# TSAL.net
KiCad netlist of a schematic drawn in Altium Designer
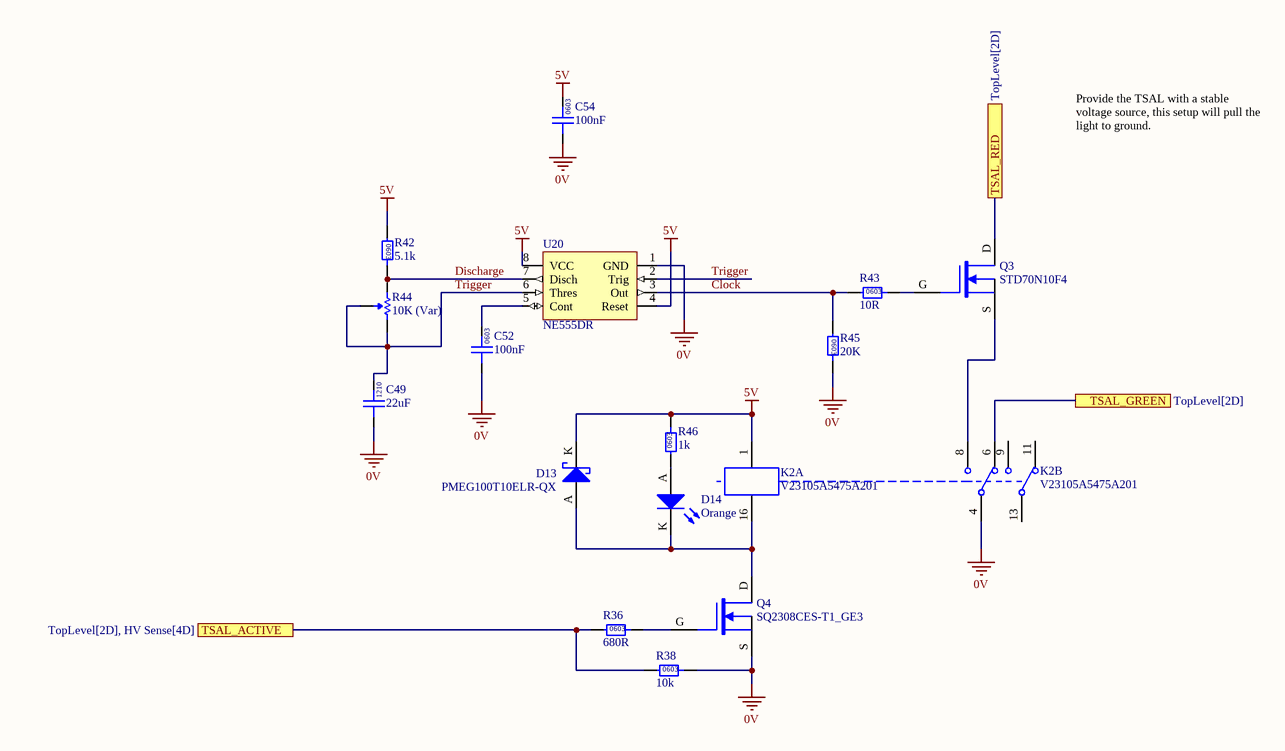
[diagram p0: TSAL.SchDoc]

(export (version "E")
  (design (tool "Eeschema 10.0.6"))
  (components
    (comp (ref "C49")
      (value "22uF")
      (footprint "1210")
      (fields
        (field (name "PART NUMBER") "GRM32ER71E226KE15L")
        (field (name "MANUFACTURER") "Murata Electronics")
        (field (name "TOLERANCE") "±10%")
      )
      (libsource (lib "ts_standard_library") (part "Capacitor 1210"))
    )
    (comp (ref "C52")
      (value "100nF")
      (footprint "0603")
      (fields
        (field (name "PART NUMBER") "GCM188L81H104KA57D")
        (field (name "MANUFACTURER") "muRata")
        (field (name "TOLERANCE") "±10%")
      )
      (libsource (lib "ts_standard_library") (part "Capacitor 0603"))
    )
    (comp (ref "C54")
      (value "100nF")
      (footprint "0603")
      (fields
        (field (name "PART NUMBER") "GCM188L81H104KA57D")
        (field (name "MANUFACTURER") "muRata")
        (field (name "TOLERANCE") "±10%")
      )
      (libsource (lib "ts_standard_library") (part "Capacitor 0603"))
    )
    (comp (ref "D13")
      (value "PMEG100T10ELR-QX")
      (footprint "NXP SOD123W")
      (fields
        (field (name "MANUFACTURER") "Nexperia USA Inc.")
        (field (name "DIGIKEY PART NUMBER") "1727-PMEG100T10ELR-QXCT-ND")
      )
      (libsource (lib "ts_standard_library") (part "Diode (Schottky)"))
    )
    (comp (ref "D14")
      (value "Orange")
      (footprint "0805 LED")
      (description "Orange LED Indication - Discrete 1.75V 0805 (2012 Metric)")
      (fields (field (name "PART NUMBER") "SML-211DTT86") (field (name "MANUFACTURER") "ROHM Semiconductor"))
      (libsource (lib "ts_standard_library") (part "LED"))
    )
    (comp (ref "K2")
      (value "V23105A5475A201")
      (footprint "TI 2-DIL")
      (description "5V DPDT Relay 3A 220VDC")
      (libsource (lib "") (part "Symbol_1"))
    )
    (comp (ref "Q3")
      (value "STD70N10F4")
      (footprint "STM TO-252 MOSFET")
      (description "N-Channel 100V 60A (Tc) 125W (Tc) Surface Mount DPAK")
      (fields
        (field (name "MANUFACTURER") "STMicroelectronics")
        (field (name "DIGIKEY PART NUMBER") "497-8806-2-ND")
        (field (name "PUBLISHER") "Altium Limited")
      )
      (libsource (lib "ts_standard_library") (part "MOSFET-N"))
    )
    (comp (ref "Q4")
      (value "SQ2308CES-T1_GE3")
      (footprint "VSHY SOT-23-3")
      (description "MOSFET N-CH 60V 2.3A SOT23")
      (fields
        (field (name "MANUFACTURER") "Vishay Siliconix")
        (field (name "DIGIKEY PART NUMBER") "SQ2308CES-T1_GE3CT-ND")
        (field (name "PUBLISHER") "Altium Limited")
      )
      (libsource (lib "ts_standard_library") (part "MOSFET-N"))
    )
    (comp (ref "R36")
      (value "680R")
      (footprint "0603")
      (fields
        (field (name "PART NUMBER") "RC0603JR-13680RL")
        (field (name "MANUFACTURER") "YAGEO")
        (field (name "TOLERANCE") "0.01")
      )
      (libsource (lib "ts_standard_library") (part "Resistor 0603"))
    )
    (comp (ref "R38")
      (value "10k")
      (footprint "0603")
      (fields
        (field (name "PART NUMBER") "RC0603FR-0710KL")
        (field (name "MANUFACTURER") "YAGEO")
        (field (name "TOLERANCE") "0.01")
      )
      (libsource (lib "ts_standard_library") (part "Resistor 0603"))
    )
    (comp (ref "R42")
      (value "5.1k")
      (footprint "0603")
      (fields
        (field (name "PART NUMBER") "RC0603JR-075K1L")
        (field (name "MANUFACTURER") "YAGEO")
        (field (name "TOLERANCE") "0.01")
      )
      (libsource (lib "ts_standard_library") (part "Resistor 0603"))
    )
    (comp (ref "R43")
      (value "10R")
      (footprint "0603")
      (fields
        (field (name "PART NUMBER") "RC0603FR-0710RL")
        (field (name "MANUFACTURER") "YAGEO")
        (field (name "TOLERANCE") "0.01")
      )
      (libsource (lib "ts_standard_library") (part "Resistor 0603"))
    )
    (comp (ref "R44")
      (value "10K (Var)")
      (footprint "B 3296")
      (fields
        (field (name "PART NUMBER") "3296W-1-103LF")
        (field (name "MANUFACTURER") "Bournes Inc")
        (field (name "TOLERANCE") "0.1")
      )
      (libsource (lib "ts_standard_library") (part "Resistor (Potentiometer)"))
    )
    (comp (ref "R45")
      (value "20K")
      (footprint "0603")
      (fields
        (field (name "PART NUMBER") "RC0603FR-0720KL")
        (field (name "MANUFACTURER") "YAGEO")
        (field (name "TOLERANCE") "0.01")
      )
      (libsource (lib "ts_standard_library") (part "Resistor 0603"))
    )
    (comp (ref "R46")
      (value "1k")
      (footprint "0603")
      (fields
        (field (name "PART NUMBER") "RC0603FR-071KL")
        (field (name "MANUFACTURER") "YAGEO")
        (field (name "TOLERANCE") "0.01")
      )
      (libsource (lib "ts_standard_library") (part "Resistor 0603"))
    )
    (comp (ref "U20")
      (value "NE555DR")
      (footprint "TI 8-SOIC")
      (description "IC OSC SGL TIMER 100KHZ 8-SOIC")
      (libsource (lib "Team Swinburne") (part "NE555DR"))
    )
  )
  (nets
    (net (code "1") (name "/Clock") (class "Default")
      (node (ref "R43") (pin "1") (pinfunction "1_1") (pintype "passive"))
      (node (ref "R45") (pin "1") (pinfunction "1_1") (pintype "passive"))
      (node (ref "U20") (pin "3") (pinfunction "Out_3") (pintype "output"))
    )
    (net (code "2") (name "/Discharge") (class "Default")
      (node (ref "R42") (pin "2") (pinfunction "2_2") (pintype "passive"))
      (node (ref "R44") (pin "3") (pinfunction "CW_3") (pintype "passive"))
      (node (ref "U20") (pin "7") (pinfunction "Disch_7") (pintype "output"))
    )
    (net (code "3") (name "/TSAL_ACTIVE") (class "Default")
      (node (ref "R36") (pin "1") (pinfunction "1_1") (pintype "passive"))
      (node (ref "R38") (pin "1") (pinfunction "1_1") (pintype "passive"))
    )
    (net (code "4") (name "/TSAL_GREEN") (class "Default")
      (node (ref "K2") (pin "6") (pinfunction "6_6") (pintype "passive"))
    )
    (net (code "5") (name "/TSAL_RED") (class "Default")
      (node (ref "Q3") (pin "D") (pinfunction "D_D") (pintype "passive"))
    )
    (net (code "6") (name "/Trigger") (class "Default")
      (node (ref "C49") (pin "2") (pinfunction "2_2") (pintype "passive"))
      (node (ref "R44") (pin "1") (pinfunction "CCW_1") (pintype "passive"))
      (node (ref "R44") (pin "2") (pinfunction "Wiper_2") (pintype "passive"))
      (node (ref "U20") (pin "2") (pinfunction "Trig_2") (pintype "input"))
      (node (ref "U20") (pin "6") (pinfunction "Thres_6") (pintype "input"))
    )
    (net (code "7") (name "0V") (class "Default")
      (node (ref "C49") (pin "1") (pinfunction "1_1") (pintype "passive"))
      (node (ref "C52") (pin "1") (pinfunction "1_1") (pintype "passive"))
      (node (ref "C54") (pin "1") (pinfunction "1_1") (pintype "passive"))
      (node (ref "K2") (pin "4") (pinfunction "4_4") (pintype "passive"))
      (node (ref "Q4") (pin "S") (pinfunction "S_S") (pintype "passive"))
      (node (ref "R38") (pin "2") (pinfunction "2_2") (pintype "passive"))
      (node (ref "R45") (pin "2") (pinfunction "2_2") (pintype "passive"))
      (node (ref "U20") (pin "1") (pinfunction "GND_1") (pintype "power_in"))
    )
    (net (code "8") (name "5V") (class "Default")
      (node (ref "C54") (pin "2") (pinfunction "2_2") (pintype "passive"))
      (node (ref "D13") (pin "K") (pinfunction "K_K") (pintype "passive"))
      (node (ref "K2") (pin "1") (pinfunction "1_1") (pintype "passive"))
      (node (ref "R42") (pin "1") (pinfunction "1_1") (pintype "passive"))
      (node (ref "R46") (pin "2") (pinfunction "2_2") (pintype "passive"))
      (node (ref "U20") (pin "4") (pinfunction "Reset_4") (pintype "passive"))
      (node (ref "U20") (pin "8") (pinfunction "VCC_8") (pintype "passive"))
    )
    (net (code "9") (name "Net-(D13-PadA)") (class "Default")
      (node (ref "D13") (pin "A") (pinfunction "A_A") (pintype "passive"))
      (node (ref "D14") (pin "K") (pinfunction "K_K") (pintype "passive"))
      (node (ref "K2") (pin "16") (pinfunction "16_16") (pintype "passive"))
      (node (ref "Q4") (pin "D") (pinfunction "D_D") (pintype "passive"))
    )
    (net (code "10") (name "Net-(D14-PadA)") (class "Default")
      (node (ref "D14") (pin "A") (pinfunction "A_A") (pintype "passive"))
      (node (ref "R46") (pin "1") (pinfunction "1_1") (pintype "passive"))
    )
    (net (code "11") (name "Net-(K2-Pad8)") (class "Default")
      (node (ref "K2") (pin "8") (pinfunction "8_8") (pintype "passive"))
      (node (ref "Q3") (pin "S") (pinfunction "S_S") (pintype "passive"))
    )
    (net (code "12") (name "Net-(Q3-PadG)") (class "Default")
      (node (ref "Q3") (pin "G") (pinfunction "G_G") (pintype "passive"))
      (node (ref "R43") (pin "2") (pinfunction "2_2") (pintype "passive"))
    )
    (net (code "13") (name "Net-(Q4-PadG)") (class "Default")
      (node (ref "Q4") (pin "G") (pinfunction "G_G") (pintype "passive"))
      (node (ref "R36") (pin "2") (pinfunction "2_2") (pintype "passive"))
    )
    (net (code "14") (name "Net-(U20-Cont)") (class "Default")
      (node (ref "C52") (pin "2") (pinfunction "2_2") (pintype "passive"))
      (node (ref "U20") (pin "5") (pinfunction "Cont_5") (pintype "bidirectional"))
    )
    (net (code "15") (name "unconnected-(K2-Pad9)") (class "Default")
      (node (ref "K2") (pin "9") (pinfunction "9_9") (pintype "passive"))
    )
    (net (code "16") (name "unconnected-(K2-Pad11)") (class "Default")
      (node (ref "K2") (pin "11") (pinfunction "11_11") (pintype "passive"))
    )
    (net (code "17") (name "unconnected-(K2-Pad13)") (class "Default")
      (node (ref "K2") (pin "13") (pinfunction "13_13") (pintype "passive"))
    )
  )
)
